# End_OptoSwitch.net
KiCad netlist of a schematic drawn in Altium Designer
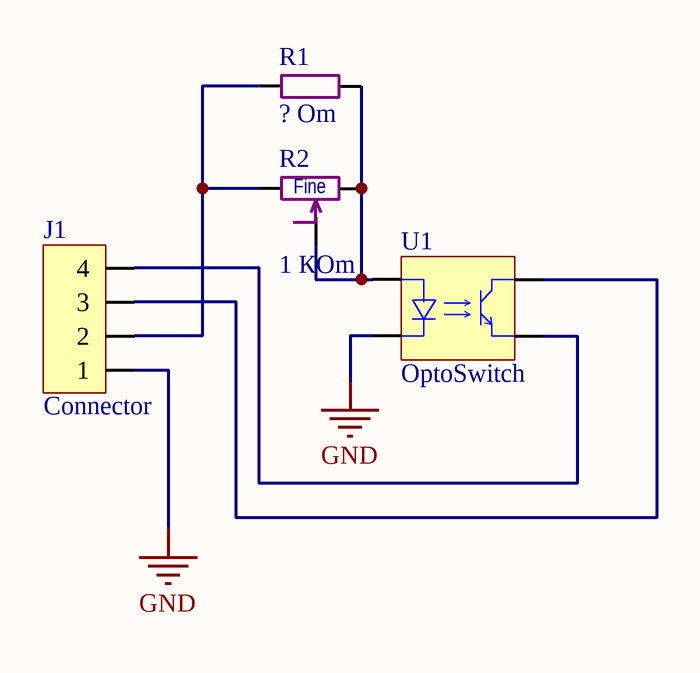
[diagram p0: End OptoSwitch.SchDoc]

(export (version "E")
  (design (tool "Eeschema 10.0.6"))
  (components
    (comp (ref "J1")
      (value "Connector")
      (footprint "Connector:Molex Micro-Fit 3.0 - 4 pin D R")
      (description "Horisontal, Dbl line, Male - 3mm")
      (fields (field (name "PART NUMBER") "0430450402"))
      (libsource (lib "Connector") (part "Micro-Fit 4R (2x2)"))
    )
    (comp (ref "R1")
      (value "? Om")
      (footprint "PassiveComponents:SMD 0805 (2012)")
      (libsource (lib "PassiveComponents") (part "Res SMD 0805"))
    )
    (comp (ref "R2")
      (value "1 КOm")
      (footprint "PassiveComponents:Res Adj 3296 Univ")
      (libsource (lib "PassiveComponents") (part "Res Adj 3296"))
    )
    (comp (ref "U1")
      (value "OptoSwitch")
      (footprint "LED:OptoSwitch")
      (libsource (lib "Transistor") (part "Optocouplier (Switch)"))
    )
  )
  (nets
    (net (code "1") (name "GND") (class "Default")
      (node (ref "J1") (pin "1") (pinfunction "1_1") (pintype "passive"))
      (node (ref "U1") (pin "K") (pinfunction "K_K") (pintype "passive"))
    )
    (net (code "2") (name "Net-(J1-Pad2)") (class "Default")
      (node (ref "J1") (pin "2") (pinfunction "2_2") (pintype "passive"))
      (node (ref "R1") (pin "1") (pinfunction "1_1") (pintype "passive"))
      (node (ref "R2") (pin "1") (pinfunction "1_1") (pintype "passive"))
    )
    (net (code "3") (name "Net-(J1-Pad3)") (class "Default")
      (node (ref "J1") (pin "3") (pinfunction "3_3") (pintype "passive"))
      (node (ref "U1") (pin "C") (pinfunction "C_C") (pintype "passive"))
    )
    (net (code "4") (name "Net-(J1-Pad4)") (class "Default")
      (node (ref "J1") (pin "4") (pinfunction "4_4") (pintype "passive"))
      (node (ref "U1") (pin "E") (pinfunction "E_E") (pintype "passive"))
    )
    (net (code "5") (name "Net-(R1-Pad2)") (class "Default")
      (node (ref "R1") (pin "2") (pinfunction "2_2") (pintype "passive"))
      (node (ref "R2") (pin "2") (pinfunction "2_2") (pintype "passive"))
      (node (ref "R2") (pin "3") (pinfunction "3_3") (pintype "passive"))
      (node (ref "U1") (pin "A") (pinfunction "A_A") (pintype "passive"))
    )
  )
)
